# sensor_board_v0_5.net
KiCad netlist of a schematic drawn in EAGLE
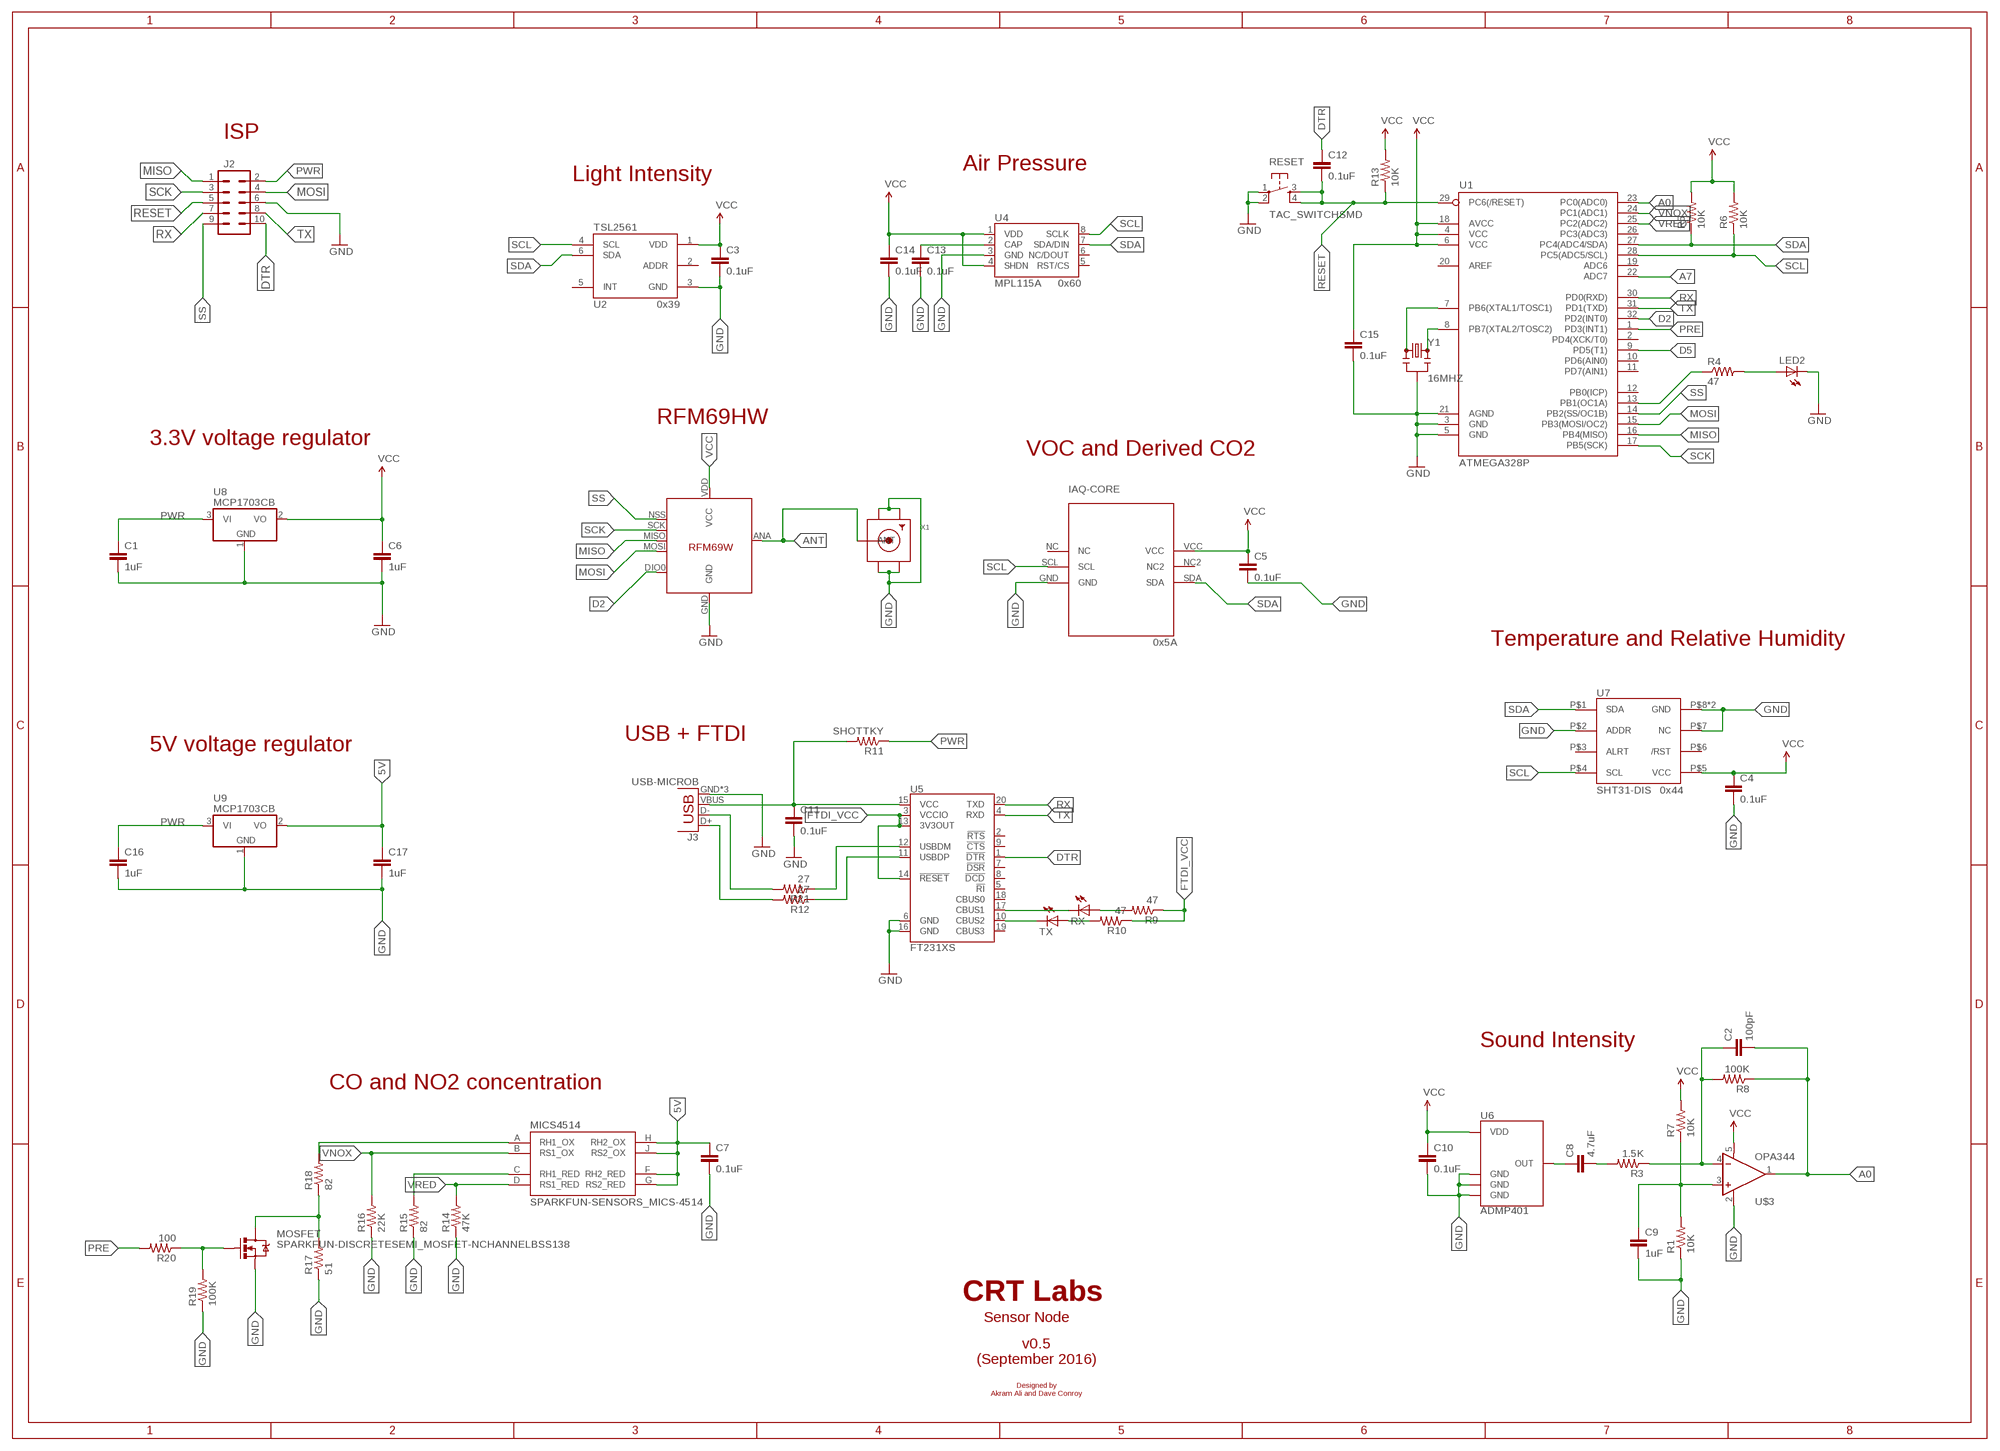
[diagram p0: schematic, sheet 1]

(export (version "E")
  (design (tool "Eeschema 10.0.6"))
  (components
    (comp (ref "C1")
      (value "1uF")
      (footprint "eagle-import:0805")
      (libsource (lib "eagle-import") (part "CAP0805"))
    )
    (comp (ref "C2")
      (value "100pF")
      (footprint "eagle-import:0805")
      (libsource (lib "eagle-import") (part "CAP0805"))
    )
    (comp (ref "C3")
      (value "0.1uF")
      (footprint "eagle-import:0805")
      (libsource (lib "eagle-import") (part "SparkFun-Passives_CAP0805"))
    )
    (comp (ref "C4")
      (value "0.1uF")
      (footprint "eagle-import:0805")
      (libsource (lib "eagle-import") (part "SparkFun-Passives_CAP0805"))
    )
    (comp (ref "C5")
      (value "0.1uF")
      (footprint "eagle-import:0805")
      (libsource (lib "eagle-import") (part "SparkFun-Passives_CAP0805"))
    )
    (comp (ref "C6")
      (value "1uF")
      (footprint "eagle-import:0805")
      (libsource (lib "eagle-import") (part "CAP0805"))
    )
    (comp (ref "C7")
      (value "0.1uF")
      (footprint "eagle-import:0805")
      (libsource (lib "eagle-import") (part "SparkFun-Passives_CAP0805"))
    )
    (comp (ref "C8")
      (value "4.7uF")
      (footprint "eagle-import:0805")
      (libsource (lib "eagle-import") (part "CAP0805"))
    )
    (comp (ref "C9")
      (value "1uF")
      (footprint "eagle-import:0805")
      (libsource (lib "eagle-import") (part "CAP0805"))
    )
    (comp (ref "C10")
      (value "0.1uF")
      (footprint "eagle-import:0805")
      (libsource (lib "eagle-import") (part "CAP0805"))
    )
    (comp (ref "C11")
      (value "0.1uF")
      (footprint "eagle-import:0805")
      (libsource (lib "eagle-import") (part "CAP0805"))
    )
    (comp (ref "C12")
      (value "0.1uF")
      (footprint "eagle-import:0805")
      (libsource (lib "eagle-import") (part "SparkFun-Passives_CAP0805"))
    )
    (comp (ref "C13")
      (value "0.1uF")
      (footprint "eagle-import:0805")
      (libsource (lib "eagle-import") (part "SparkFun-Passives_CAP0805"))
    )
    (comp (ref "C14")
      (value "0.1uF")
      (footprint "eagle-import:0805")
      (libsource (lib "eagle-import") (part "SparkFun-Passives_CAP0805"))
    )
    (comp (ref "C15")
      (value "0.1uF")
      (footprint "eagle-import:0805")
      (libsource (lib "eagle-import") (part "SparkFun-Passives_CAP0805"))
    )
    (comp (ref "C16")
      (value "1uF")
      (footprint "eagle-import:0805")
      (libsource (lib "eagle-import") (part "CAP0805"))
    )
    (comp (ref "C17")
      (value "1uF")
      (footprint "eagle-import:0805")
      (libsource (lib "eagle-import") (part "CAP0805"))
    )
    (comp (ref "IAQ-CORE")
      (value "IAQ-CORE")
      (footprint "eagle-import:IAQ-CORE")
      (fields (field (name "MPN") "IAQ CORE"))
      (libsource (lib "eagle-import") (part "IAQ-CORE"))
    )
    (comp (ref "J2")
      (value "M05X2PTH")
      (footprint "eagle-import:AVR_ICSP")
      (libsource (lib "eagle-import") (part "M05X2PTH"))
    )
    (comp (ref "J3")
      (value "USB-MICROB")
      (footprint "eagle-import:USB-MICROB")
      (libsource (lib "eagle-import") (part "USB-MICROB"))
    )
    (comp (ref "LED2")
      (value "LEDCHIPLED_0805")
      (footprint "eagle-import:CHIPLED_0805")
      (libsource (lib "eagle-import") (part "LEDCHIPLED_0805"))
    )
    (comp (ref "MICS4514")
      (value "SPARKFUN-SENSORS_MICS-4514")
      (footprint "eagle-import:SPARKFUN-SENSORS_MICS_10-SMD")
      (libsource (lib "eagle-import") (part "SPARKFUN-SENSORS_MICS-4514"))
    )
    (comp (ref "MOSFET")
      (value "SPARKFUN-DISCRETESEMI_MOSFET-NCHANNELBSS138")
      (footprint "eagle-import:SPARKFUN-DISCRETESEMI_SOT23-3")
      (libsource (lib "eagle-import") (part "SPARKFUN-DISCRETESEMI_MOSFET-NCHANNELBSS138"))
    )
    (comp (ref "R1")
      (value "10K")
      (footprint "eagle-import:0805")
      (libsource (lib "eagle-import") (part "RESISTOR0805-RES"))
    )
    (comp (ref "R3")
      (value "1.5K")
      (footprint "eagle-import:0805")
      (libsource (lib "eagle-import") (part "RESISTOR0805-RES"))
    )
    (comp (ref "R4")
      (value "47")
      (footprint "eagle-import:0805")
      (libsource (lib "eagle-import") (part "SparkFun-Resistors_RESISTOR0805-RES"))
    )
    (comp (ref "R5")
      (value "10K")
      (footprint "eagle-import:0805")
      (libsource (lib "eagle-import") (part "SparkFun-Resistors_RESISTOR0805-RES"))
    )
    (comp (ref "R6")
      (value "10K")
      (footprint "eagle-import:0805")
      (libsource (lib "eagle-import") (part "SparkFun-Resistors_RESISTOR0805-RES"))
    )
    (comp (ref "R7")
      (value "10K")
      (footprint "eagle-import:0805")
      (libsource (lib "eagle-import") (part "RESISTOR0805-RES"))
    )
    (comp (ref "R8")
      (value "100K")
      (footprint "eagle-import:0805")
      (libsource (lib "eagle-import") (part "RESISTOR0805-RES"))
    )
    (comp (ref "R9")
      (value "47")
      (footprint "eagle-import:0805")
      (libsource (lib "eagle-import") (part "RESISTOR0805-RES"))
    )
    (comp (ref "R10")
      (value "47")
      (footprint "eagle-import:0805")
      (libsource (lib "eagle-import") (part "RESISTOR0805-RES"))
    )
    (comp (ref "R11")
      (value "SHOTTKY")
      (footprint "eagle-import:0805")
      (libsource (lib "eagle-import") (part "RESISTOR0805-RES"))
    )
    (comp (ref "R12")
      (value "27")
      (footprint "eagle-import:0805")
      (libsource (lib "eagle-import") (part "RESISTOR0805-RES"))
    )
    (comp (ref "R13")
      (value "10K")
      (footprint "eagle-import:0805")
      (libsource (lib "eagle-import") (part "RESISTOR0805-RES"))
    )
    (comp (ref "R14")
      (value "47K")
      (footprint "eagle-import:0805")
      (libsource (lib "eagle-import") (part "RESISTOR0805-RES"))
    )
    (comp (ref "R15")
      (value "82")
      (footprint "eagle-import:0805")
      (libsource (lib "eagle-import") (part "RESISTOR0805-RES"))
    )
    (comp (ref "R16")
      (value "22K")
      (footprint "eagle-import:0805")
      (libsource (lib "eagle-import") (part "RESISTOR0805-RES"))
    )
    (comp (ref "R17")
      (value "51")
      (footprint "eagle-import:0805")
      (libsource (lib "eagle-import") (part "RESISTOR0805-RES"))
    )
    (comp (ref "R18")
      (value "82")
      (footprint "eagle-import:0805")
      (libsource (lib "eagle-import") (part "RESISTOR0805-RES"))
    )
    (comp (ref "R19")
      (value "100K")
      (footprint "eagle-import:0805")
      (libsource (lib "eagle-import") (part "RESISTOR0805-RES"))
    )
    (comp (ref "R20")
      (value "100")
      (footprint "eagle-import:0805")
      (libsource (lib "eagle-import") (part "RESISTOR0805-RES"))
    )
    (comp (ref "R21")
      (value "27")
      (footprint "eagle-import:0805")
      (libsource (lib "eagle-import") (part "RESISTOR0805-RES"))
    )
    (comp (ref "RESET")
      (value "TAC_SWITCHSMD")
      (footprint "eagle-import:TACTILE-SWITCH-SMD")
      (libsource (lib "eagle-import") (part "TAC_SWITCHSMD"))
    )
    (comp (ref "RX")
      (value "LEDCHIPLED_0805")
      (footprint "eagle-import:CHIPLED_0805")
      (libsource (lib "eagle-import") (part "LEDCHIPLED_0805"))
    )
    (comp (ref "TX")
      (value "LEDCHIPLED_0805")
      (footprint "eagle-import:CHIPLED_0805")
      (libsource (lib "eagle-import") (part "LEDCHIPLED_0805"))
    )
    (comp (ref "U$3")
      (value "OPA344")
      (footprint "eagle-import:SOT23-5")
      (libsource (lib "eagle-import") (part "OPA344"))
    )
    (comp (ref "U$4")
      (value "RFM69HW")
      (footprint "eagle-import:LOWPOWERLAB_RFM69W-MINPADS")
      (libsource (lib "eagle-import") (part "LOWPOWERLAB_RFM69"))
    )
    (comp (ref "U1")
      (value "ATMEGA328P")
      (footprint "eagle-import:TQFP32-08")
      (fields (field (name "MPN") "ATMEGA328PB-AU"))
      (libsource (lib "eagle-import") (part "ATMEGA328P_TQFP"))
    )
    (comp (ref "U2")
      (value "TSL2561")
      (footprint "eagle-import:FN-6")
      (fields (field (name "MANF") "AMS-TAOS-USA-Inc.") (field (name "MPN") "TSL2561FN"))
      (libsource (lib "eagle-import") (part "TSL2561FN"))
    )
    (comp (ref "U4")
      (value "MPL115A")
      (footprint "eagle-import:LGA8")
      (libsource (lib "eagle-import") (part "MPL115A"))
    )
    (comp (ref "U5")
      (value "FT231XS")
      (footprint "eagle-import:SSOP20_L")
      (libsource (lib "eagle-import") (part "FT231XS"))
    )
    (comp (ref "U6")
      (value "ADMP401")
      (footprint "eagle-import:ADMP401")
      (libsource (lib "eagle-import") (part "ADMP401"))
    )
    (comp (ref "U7")
      (value "SHT31-DIS")
      (footprint "eagle-import:SHT3X")
      (fields (field (name "MPN") "SHT31-DIS-B"))
      (libsource (lib "eagle-import") (part "SHT31-DIS"))
    )
    (comp (ref "U8")
      (value "MCP1703CB")
      (footprint "eagle-import:SOT23")
      (fields (field (name "MPN") "MCP1703T-2502E/CB"))
      (libsource (lib "eagle-import") (part "MCP1703CB"))
    )
    (comp (ref "U9")
      (value "MCP1703CB")
      (footprint "eagle-import:SOT23")
      (fields (field (name "MPN") "MCP1703T-2502E/CB"))
      (libsource (lib "eagle-import") (part "MCP1703CB"))
    )
    (comp (ref "X1")
      (value "SMACONNECTOR_EDGE")
      (footprint "eagle-import:SMA_EDGELAUNCH")
      (libsource (lib "eagle-import") (part "SMACONNECTOR_EDGE"))
    )
    (comp (ref "Y1")
      (value "16MHZ")
      (footprint "eagle-import:RESONATOR-SMD")
      (libsource (lib "eagle-import") (part "RESONATOR16MHZ"))
    )
  )
  (nets
    (net (code "1") (name "5V") (class "Default")
      (node (ref "C17") (pin "1") (pinfunction "1_1") (pintype "passive"))
      (node (ref "C7") (pin "1") (pinfunction "1_1") (pintype "passive"))
      (node (ref "MICS4514") (pin "F") (pinfunction "RH2_RED_F") (pintype "bidirectional"))
      (node (ref "MICS4514") (pin "G") (pinfunction "RS2_RED_G") (pintype "bidirectional"))
      (node (ref "MICS4514") (pin "H") (pinfunction "RH2_OX_H") (pintype "bidirectional"))
      (node (ref "MICS4514") (pin "J") (pinfunction "RS2_OX_J") (pintype "bidirectional"))
      (node (ref "U9") (pin "2") (pinfunction "VO_2") (pintype "passive"))
    )
    (net (code "2") (name "A0") (class "Default")
      (node (ref "C2") (pin "2") (pinfunction "2_2") (pintype "passive"))
      (node (ref "R8") (pin "1") (pinfunction "1_1") (pintype "passive"))
      (node (ref "U$3") (pin "1") (pinfunction "OUT_1") (pintype "output"))
      (node (ref "U1") (pin "23") (pinfunction "PC0(ADC0)_23") (pintype "bidirectional"))
    )
    (net (code "3") (name "A7") (class "Default")
      (node (ref "U1") (pin "22") (pinfunction "ADC7_22") (pintype "bidirectional"))
    )
    (net (code "4") (name "ANT") (class "Default")
      (node (ref "U$4") (pin "ANA") (pinfunction "ANT_ANA") (pintype "passive"))
      (node (ref "X1") (pin "P") (pinfunction "ANT_P") (pintype "bidirectional"))
    )
    (net (code "5") (name "D2") (class "Default")
      (node (ref "U$4") (pin "DIO0") (pinfunction "DIO0_DIO0") (pintype "open_collector"))
      (node (ref "U1") (pin "32") (pinfunction "PD2(INT0)_32") (pintype "bidirectional"))
    )
    (net (code "6") (name "D5") (class "Default")
      (node (ref "U1") (pin "9") (pinfunction "PD5(T1)_9") (pintype "bidirectional"))
    )
    (net (code "7") (name "DTR") (class "Default")
      (node (ref "C12") (pin "1") (pinfunction "1_1") (pintype "passive"))
      (node (ref "J2") (pin "10") (pinfunction "10_10") (pintype "passive"))
      (node (ref "U5") (pin "1") (pinfunction "~{DTR}_1") (pintype "bidirectional"))
    )
    (net (code "8") (name "FTDI_VCC") (class "Default")
      (node (ref "R10") (pin "1") (pinfunction "1_1") (pintype "passive"))
      (node (ref "R9") (pin "1") (pinfunction "1_1") (pintype "passive"))
      (node (ref "U5") (pin "13") (pinfunction "3V3OUT_13") (pintype "bidirectional"))
      (node (ref "U5") (pin "14") (pinfunction "~{RESET}_14") (pintype "bidirectional"))
      (node (ref "U5") (pin "3") (pinfunction "VCCIO_3") (pintype "bidirectional"))
    )
    (net (code "9") (name "GND") (class "Default")
      (node (ref "C1") (pin "2") (pinfunction "2_2") (pintype "passive"))
      (node (ref "C10") (pin "2") (pinfunction "2_2") (pintype "passive"))
      (node (ref "C11") (pin "2") (pinfunction "2_2") (pintype "passive"))
      (node (ref "C13") (pin "2") (pinfunction "2_2") (pintype "passive"))
      (node (ref "C14") (pin "2") (pinfunction "2_2") (pintype "passive"))
      (node (ref "C15") (pin "2") (pinfunction "2_2") (pintype "passive"))
      (node (ref "C16") (pin "2") (pinfunction "2_2") (pintype "passive"))
      (node (ref "C17") (pin "2") (pinfunction "2_2") (pintype "passive"))
      (node (ref "C3") (pin "2") (pinfunction "2_2") (pintype "passive"))
      (node (ref "C4") (pin "2") (pinfunction "2_2") (pintype "passive"))
      (node (ref "C5") (pin "2") (pinfunction "2_2") (pintype "passive"))
      (node (ref "C6") (pin "2") (pinfunction "2_2") (pintype "passive"))
      (node (ref "C7") (pin "2") (pinfunction "2_2") (pintype "passive"))
      (node (ref "C9") (pin "2") (pinfunction "2_2") (pintype "passive"))
      (node (ref "IAQ-CORE") (pin "GND") (pinfunction "GND_GND") (pintype "bidirectional"))
      (node (ref "J2") (pin "6") (pinfunction "6_6") (pintype "passive"))
      (node (ref "J3") (pin "GND") (pinfunction "GND_GND") (pintype "bidirectional"))
      (node (ref "J3") (pin "MT1") (pinfunction "GND_MT1") (pintype "bidirectional"))
      (node (ref "J3") (pin "MT2") (pinfunction "GND_MT2") (pintype "bidirectional"))
      (node (ref "LED2") (pin "C") (pinfunction "C_C") (pintype "passive"))
      (node (ref "MOSFET") (pin "2") (pinfunction "S_2") (pintype "passive"))
      (node (ref "R1") (pin "1") (pinfunction "1_1") (pintype "passive"))
      (node (ref "R14") (pin "1") (pinfunction "1_1") (pintype "passive"))
      (node (ref "R15") (pin "1") (pinfunction "1_1") (pintype "passive"))
      (node (ref "R16") (pin "1") (pinfunction "1_1") (pintype "passive"))
      (node (ref "R17") (pin "1") (pinfunction "1_1") (pintype "passive"))
      (node (ref "R19") (pin "1") (pinfunction "1_1") (pintype "passive"))
      (node (ref "RESET") (pin "1") (pinfunction "1_1") (pintype "passive"))
      (node (ref "RESET") (pin "2") (pinfunction "2_2") (pintype "passive"))
      (node (ref "U$3") (pin "2") (pinfunction "V-_2") (pintype "power_in"))
      (node (ref "U$4") (pin "GND") (pinfunction "GND_GND") (pintype "power_in"))
      (node (ref "U1") (pin "21") (pinfunction "AGND_21") (pintype "bidirectional"))
      (node (ref "U1") (pin "3") (pinfunction "GND_3") (pintype "bidirectional"))
      (node (ref "U1") (pin "5") (pinfunction "GND_5") (pintype "bidirectional"))
      (node (ref "U2") (pin "3") (pinfunction "GND_3") (pintype "power_in"))
      (node (ref "U4") (pin "3") (pinfunction "GND_3") (pintype "bidirectional"))
      (node (ref "U5") (pin "16") (pinfunction "GND_16") (pintype "bidirectional"))
      (node (ref "U5") (pin "6") (pinfunction "GND_6") (pintype "bidirectional"))
      (node (ref "U6") (pin "2") (pinfunction "GND_2") (pintype "bidirectional"))
      (node (ref "U6") (pin "4") (pinfunction "GND_4") (pintype "bidirectional"))
      (node (ref "U6") (pin "6") (pinfunction "GND_6") (pintype "bidirectional"))
      (node (ref "U7") (pin "P$2") (pinfunction "ADDR_P$2") (pintype "bidirectional"))
      (node (ref "U7") (pin "P$7") (pinfunction "NC_P$7") (pintype "bidirectional"))
      (node (ref "U7") (pin "P$8") (pinfunction "GND_P$8") (pintype "bidirectional"))
      (node (ref "U7") (pin "PAD") (pinfunction "GND_PAD") (pintype "bidirectional"))
      (node (ref "U8") (pin "1") (pinfunction "GND_1") (pintype "passive"))
      (node (ref "U9") (pin "1") (pinfunction "GND_1") (pintype "passive"))
      (node (ref "X1") (pin "GND@1") (pinfunction "GND4_GND@1") (pintype "power_in"))
      (node (ref "X1") (pin "GND@2") (pinfunction "GND3_GND@2") (pintype "power_in"))
      (node (ref "X1") (pin "GND@3") (pinfunction "GND2_GND@3") (pintype "power_in"))
      (node (ref "X1") (pin "GND@4") (pinfunction "GND1_GND@4") (pintype "power_in"))
      (node (ref "Y1") (pin "2") (pinfunction "2_2") (pintype "passive"))
    )
    (net (code "10") (name "MISO") (class "Default")
      (node (ref "J2") (pin "1") (pinfunction "1_1") (pintype "passive"))
      (node (ref "U$4") (pin "MISO") (pinfunction "MISO_MISO") (pintype "input"))
      (node (ref "U1") (pin "16") (pinfunction "PB4(MISO)_16") (pintype "bidirectional"))
    )
    (net (code "11") (name "MOSI") (class "Default")
      (node (ref "J2") (pin "4") (pinfunction "4_4") (pintype "passive"))
      (node (ref "U$4") (pin "MOSI") (pinfunction "MOSI_MOSI") (pintype "output"))
      (node (ref "U1") (pin "15") (pinfunction "PB3(MOSI/OC2)_15") (pintype "bidirectional"))
    )
    (net (code "12") (name "Net-(C8-Pad2)") (class "Default")
      (node (ref "C8") (pin "2") (pinfunction "2_2") (pintype "passive"))
      (node (ref "R3") (pin "2") (pinfunction "2_2") (pintype "passive"))
    )
    (net (code "13") (name "Net-(J3-PadD+)") (class "Default")
      (node (ref "J3") (pin "D+") (pinfunction "D+_D+") (pintype "bidirectional"))
      (node (ref "R12") (pin "2") (pinfunction "2_2") (pintype "passive"))
    )
    (net (code "14") (name "Net-(J3-PadD-)") (class "Default")
      (node (ref "J3") (pin "D-") (pinfunction "D-_D-") (pintype "bidirectional"))
      (node (ref "R21") (pin "2") (pinfunction "2_2") (pintype "passive"))
    )
    (net (code "15") (name "Net-(LED2-PadA)") (class "Default")
      (node (ref "LED2") (pin "A") (pinfunction "A_A") (pintype "passive"))
      (node (ref "R4") (pin "2") (pinfunction "2_2") (pintype "passive"))
    )
    (net (code "16") (name "Net-(MICS4514-RH1_OX)") (class "Default")
      (node (ref "MICS4514") (pin "A") (pinfunction "RH1_OX_A") (pintype "bidirectional"))
      (node (ref "R18") (pin "2") (pinfunction "2_2") (pintype "passive"))
    )
    (net (code "17") (name "Net-(MICS4514-RH1_RED)") (class "Default")
      (node (ref "MICS4514") (pin "C") (pinfunction "RH1_RED_C") (pintype "bidirectional"))
      (node (ref "R15") (pin "2") (pinfunction "2_2") (pintype "passive"))
    )
    (net (code "18") (name "Net-(MOSFET-D)") (class "Default")
      (node (ref "MOSFET") (pin "3") (pinfunction "D_3") (pintype "passive"))
      (node (ref "R17") (pin "2") (pinfunction "2_2") (pintype "passive"))
      (node (ref "R18") (pin "1") (pinfunction "1_1") (pintype "passive"))
    )
    (net (code "19") (name "Net-(MOSFET-G)") (class "Default")
      (node (ref "MOSFET") (pin "1") (pinfunction "G_1") (pintype "passive"))
      (node (ref "R19") (pin "2") (pinfunction "2_2") (pintype "passive"))
      (node (ref "R20") (pin "1") (pinfunction "1_1") (pintype "passive"))
    )
    (net (code "20") (name "Net-(R9-Pad2)") (class "Default")
      (node (ref "R9") (pin "2") (pinfunction "2_2") (pintype "passive"))
      (node (ref "RX") (pin "A") (pinfunction "A_A") (pintype "passive"))
    )
    (net (code "21") (name "Net-(R10-Pad2)") (class "Default")
      (node (ref "R10") (pin "2") (pinfunction "2_2") (pintype "passive"))
      (node (ref "TX") (pin "A") (pinfunction "A_A") (pintype "passive"))
    )
    (net (code "22") (name "Net-(U$3-+IN)") (class "Default")
      (node (ref "C9") (pin "1") (pinfunction "1_1") (pintype "passive"))
      (node (ref "R1") (pin "2") (pinfunction "2_2") (pintype "passive"))
      (node (ref "R7") (pin "1") (pinfunction "1_1") (pintype "passive"))
      (node (ref "U$3") (pin "3") (pinfunction "+IN_3") (pintype "input"))
    )
    (net (code "23") (name "Net-(U$3--IN)") (class "Default")
      (node (ref "C2") (pin "1") (pinfunction "1_1") (pintype "passive"))
      (node (ref "R3") (pin "1") (pinfunction "1_1") (pintype "passive"))
      (node (ref "R8") (pin "2") (pinfunction "2_2") (pintype "passive"))
      (node (ref "U$3") (pin "4") (pinfunction "-IN_4") (pintype "input"))
    )
    (net (code "24") (name "Net-(U1-PB1(OC1A))") (class "Default")
      (node (ref "R4") (pin "1") (pinfunction "1_1") (pintype "passive"))
      (node (ref "U1") (pin "13") (pinfunction "PB1(OC1A)_13") (pintype "bidirectional"))
    )
    (net (code "25") (name "Net-(U1-PB6(XTAL1{slash}TOSC1))") (class "Default")
      (node (ref "U1") (pin "7") (pinfunction "PB6(XTAL1/TOSC1)_7") (pintype "bidirectional"))
      (node (ref "Y1") (pin "1") (pinfunction "1_1") (pintype "passive"))
    )
    (net (code "26") (name "Net-(U1-PB7(XTAL2{slash}TOSC2))") (class "Default")
      (node (ref "U1") (pin "8") (pinfunction "PB7(XTAL2/TOSC2)_8") (pintype "bidirectional"))
      (node (ref "Y1") (pin "3") (pinfunction "3_3") (pintype "passive"))
    )
    (net (code "27") (name "Net-(U4-CAP)") (class "Default")
      (node (ref "C13") (pin "1") (pinfunction "1_1") (pintype "passive"))
      (node (ref "U4") (pin "2") (pinfunction "CAP_2") (pintype "bidirectional"))
    )
    (net (code "28") (name "Net-(U5-CBUS1)") (class "Default")
      (node (ref "RX") (pin "C") (pinfunction "C_C") (pintype "passive"))
      (node (ref "U5") (pin "17") (pinfunction "CBUS1_17") (pintype "bidirectional"))
    )
    (net (code "29") (name "Net-(U5-CBUS2)") (class "Default")
      (node (ref "TX") (pin "C") (pinfunction "C_C") (pintype "passive"))
      (node (ref "U5") (pin "10") (pinfunction "CBUS2_10") (pintype "bidirectional"))
    )
    (net (code "30") (name "Net-(U5-USBDM)") (class "Default")
      (node (ref "R21") (pin "1") (pinfunction "1_1") (pintype "passive"))
      (node (ref "U5") (pin "12") (pinfunction "USBDM_12") (pintype "bidirectional"))
    )
    (net (code "31") (name "Net-(U5-USBDP)") (class "Default")
      (node (ref "R12") (pin "1") (pinfunction "1_1") (pintype "passive"))
      (node (ref "U5") (pin "11") (pinfunction "USBDP_11") (pintype "bidirectional"))
    )
    (net (code "32") (name "Net-(U5-VCC)") (class "Default")
      (node (ref "C11") (pin "1") (pinfunction "1_1") (pintype "passive"))
      (node (ref "J3") (pin "VBUS") (pinfunction "VBUS_VBUS") (pintype "bidirectional"))
      (node (ref "R11") (pin "2") (pinfunction "2_2") (pintype "passive"))
      (node (ref "U5") (pin "15") (pinfunction "VCC_15") (pintype "bidirectional"))
    )
    (net (code "33") (name "Net-(U6-OUT)") (class "Default")
      (node (ref "C8") (pin "1") (pinfunction "1_1") (pintype "passive"))
      (node (ref "U6") (pin "1") (pinfunction "OUT_1") (pintype "bidirectional"))
    )
    (net (code "34") (name "PRE") (class "Default")
      (node (ref "R20") (pin "2") (pinfunction "2_2") (pintype "passive"))
      (node (ref "U1") (pin "1") (pinfunction "PD3(INT1)_1") (pintype "bidirectional"))
    )
    (net (code "35") (name "PWR") (class "Default")
      (node (ref "C1") (pin "1") (pinfunction "1_1") (pintype "passive"))
      (node (ref "C16") (pin "1") (pinfunction "1_1") (pintype "passive"))
      (node (ref "J2") (pin "2") (pinfunction "2_2") (pintype "passive"))
      (node (ref "R11") (pin "1") (pinfunction "1_1") (pintype "passive"))
      (node (ref "U8") (pin "3") (pinfunction "VI_3") (pintype "input"))
      (node (ref "U9") (pin "3") (pinfunction "VI_3") (pintype "input"))
    )
    (net (code "36") (name "RESET") (class "Default")
      (node (ref "C12") (pin "2") (pinfunction "2_2") (pintype "passive"))
      (node (ref "J2") (pin "5") (pinfunction "5_5") (pintype "passive"))
      (node (ref "R13") (pin "1") (pinfunction "1_1") (pintype "passive"))
      (node (ref "RESET") (pin "3") (pinfunction "3_3") (pintype "passive"))
      (node (ref "RESET") (pin "4") (pinfunction "4_4") (pintype "passive"))
      (node (ref "U1") (pin "29") (pinfunction "PC6(/RESET)_29") (pintype "bidirectional"))
    )
    (net (code "37") (name "RX") (class "Default")
      (node (ref "J2") (pin "7") (pinfunction "7_7") (pintype "passive"))
      (node (ref "U1") (pin "30") (pinfunction "PD0(RXD)_30") (pintype "bidirectional"))
      (node (ref "U5") (pin "20") (pinfunction "TXD_20") (pintype "bidirectional"))
    )
    (net (code "38") (name "SCK") (class "Default")
      (node (ref "J2") (pin "3") (pinfunction "3_3") (pintype "passive"))
      (node (ref "U$4") (pin "SCK") (pinfunction "SCK_SCK") (pintype "input"))
      (node (ref "U1") (pin "17") (pinfunction "PB5(SCK)_17") (pintype "bidirectional"))
    )
    (net (code "39") (name "SCL") (class "Default")
      (node (ref "IAQ-CORE") (pin "SCL") (pinfunction "SCL_SCL") (pintype "bidirectional"))
      (node (ref "R6") (pin "1") (pinfunction "1_1") (pintype "passive"))
      (node (ref "U1") (pin "28") (pinfunction "PC5(ADC5/SCL)_28") (pintype "bidirectional"))
      (node (ref "U2") (pin "4") (pinfunction "SCL_4") (pintype "input"))
      (node (ref "U4") (pin "8") (pinfunction "SCLK_8") (pintype "bidirectional"))
      (node (ref "U7") (pin "P$4") (pinfunction "SCL_P$4") (pintype "bidirectional"))
    )
    (net (code "40") (name "SDA") (class "Default")
      (node (ref "IAQ-CORE") (pin "SDA") (pinfunction "SDA_SDA") (pintype "bidirectional"))
      (node (ref "R5") (pin "1") (pinfunction "1_1") (pintype "passive"))
      (node (ref "U1") (pin "27") (pinfunction "PC4(ADC4/SDA)_27") (pintype "bidirectional"))
      (node (ref "U2") (pin "6") (pinfunction "SDA_6") (pintype "bidirectional"))
      (node (ref "U4") (pin "7") (pinfunction "SDA/DIN_7") (pintype "bidirectional"))
      (node (ref "U7") (pin "P$1") (pinfunction "SDA_P$1") (pintype "bidirectional"))
    )
    (net (code "41") (name "SS") (class "Default")
      (node (ref "J2") (pin "9") (pinfunction "9_9") (pintype "passive"))
      (node (ref "U$4") (pin "NSS") (pinfunction "SEL_NSS") (pintype "input"))
      (node (ref "U1") (pin "14") (pinfunction "PB2(SS/OC1B)_14") (pintype "bidirectional"))
    )
    (net (code "42") (name "TX") (class "Default")
      (node (ref "J2") (pin "8") (pinfunction "8_8") (pintype "passive"))
      (node (ref "U1") (pin "31") (pinfunction "PD1(TXD)_31") (pintype "bidirectional"))
      (node (ref "U5") (pin "4") (pinfunction "RXD_4") (pintype "bidirectional"))
    )
    (net (code "43") (name "VCC") (class "Default")
      (node (ref "C10") (pin "1") (pinfunction "1_1") (pintype "passive"))
      (node (ref "C14") (pin "1") (pinfunction "1_1") (pintype "passive"))
      (node (ref "C15") (pin "1") (pinfunction "1_1") (pintype "passive"))
      (node (ref "C3") (pin "1") (pinfunction "1_1") (pintype "passive"))
      (node (ref "C4") (pin "1") (pinfunction "1_1") (pintype "passive"))
      (node (ref "C5") (pin "1") (pinfunction "1_1") (pintype "passive"))
      (node (ref "C6") (pin "1") (pinfunction "1_1") (pintype "passive"))
      (node (ref "IAQ-CORE") (pin "VCC") (pinfunction "VCC_VCC") (pintype "bidirectional"))
      (node (ref "R13") (pin "2") (pinfunction "2_2") (pintype "passive"))
      (node (ref "R5") (pin "2") (pinfunction "2_2") (pintype "passive"))
      (node (ref "R6") (pin "2") (pinfunction "2_2") (pintype "passive"))
      (node (ref "R7") (pin "2") (pinfunction "2_2") (pintype "passive"))
      (node (ref "U$3") (pin "5") (pinfunction "V+_5") (pintype "power_in"))
      (node (ref "U$4") (pin "VDD") (pinfunction "VCC_VDD") (pintype "power_in"))
      (node (ref "U1") (pin "18") (pinfunction "AVCC_18") (pintype "bidirectional"))
      (node (ref "U1") (pin "4") (pinfunction "VCC_4") (pintype "bidirectional"))
      (node (ref "U1") (pin "6") (pinfunction "VCC_6") (pintype "bidirectional"))
      (node (ref "U2") (pin "1") (pinfunction "VDD_1") (pintype "power_in"))
      (node (ref "U4") (pin "1") (pinfunction "VDD_1") (pintype "bidirectional"))
      (node (ref "U4") (pin "4") (pinfunction "SHDN_4") (pintype "bidirectional"))
      (node (ref "U6") (pin "5") (pinfunction "VDD_5") (pintype "bidirectional"))
      (node (ref "U7") (pin "P$5") (pinfunction "VCC_P$5") (pintype "bidirectional"))
      (node (ref "U8") (pin "2") (pinfunction "VO_2") (pintype "passive"))
    )
    (net (code "44") (name "VNOX") (class "Default")
      (node (ref "MICS4514") (pin "B") (pinfunction "RS1_OX_B") (pintype "bidirectional"))
      (node (ref "R16") (pin "2") (pinfunction "2_2") (pintype "passive"))
      (node (ref "U1") (pin "24") (pinfunction "PC1(ADC1)_24") (pintype "bidirectional"))
    )
    (net (code "45") (name "VRED") (class "Default")
      (node (ref "MICS4514") (pin "D") (pinfunction "RS1_RED_D") (pintype "bidirectional"))
      (node (ref "R14") (pin "2") (pinfunction "2_2") (pintype "passive"))
      (node (ref "U1") (pin "25") (pinfunction "PC2(ADC2)_25") (pintype "bidirectional"))
    )
    (net (code "46") (name "unconnected-(IAQ-CORE-PadNC)") (class "Default")
      (node (ref "IAQ-CORE") (pin "NC") (pinfunction "NC_NC") (pintype "bidirectional"))
    )
    (net (code "47") (name "unconnected-(IAQ-CORE-PadNC2)") (class "Default")
      (node (ref "IAQ-CORE") (pin "NC2") (pinfunction "NC2_NC2") (pintype "bidirectional"))
    )
    (net (code "48") (name "unconnected-(U1-ADC6-Pad19)") (class "Default")
      (node (ref "U1") (pin "19") (pinfunction "ADC6_19") (pintype "bidirectional"))
    )
    (net (code "49") (name "unconnected-(U1-AREF-Pad20)") (class "Default")
      (node (ref "U1") (pin "20") (pinfunction "AREF_20") (pintype "bidirectional"))
    )
    (net (code "50") (name "unconnected-(U1-PB0(ICP)-Pad12)") (class "Default")
      (node (ref "U1") (pin "12") (pinfunction "PB0(ICP)_12") (pintype "bidirectional"))
    )
    (net (code "51") (name "unconnected-(U1-PC3(ADC3)-Pad26)") (class "Default")
      (node (ref "U1") (pin "26") (pinfunction "PC3(ADC3)_26") (pintype "bidirectional"))
    )
    (net (code "52") (name "unconnected-(U1-PD4(XCK{slash}T0)-Pad2)") (class "Default")
      (node (ref "U1") (pin "2") (pinfunction "PD4(XCK/T0)_2") (pintype "bidirectional"))
    )
    (net (code "53") (name "unconnected-(U1-PD6(AIN0)-Pad10)") (class "Default")
      (node (ref "U1") (pin "10") (pinfunction "PD6(AIN0)_10") (pintype "bidirectional"))
    )
    (net (code "54") (name "unconnected-(U1-PD7(AIN1)-Pad11)") (class "Default")
      (node (ref "U1") (pin "11") (pinfunction "PD7(AIN1)_11") (pintype "bidirectional"))
    )
    (net (code "55") (name "unconnected-(U2-ADDR-Pad2)") (class "Default")
      (node (ref "U2") (pin "2") (pinfunction "ADDR_2") (pintype "input"))
    )
    (net (code "56") (name "unconnected-(U2-INT-Pad5)") (class "Default")
      (node (ref "U2") (pin "5") (pinfunction "INT_5") (pintype "output"))
    )
    (net (code "57") (name "unconnected-(U4-NC{slash}DOUT-Pad6)") (class "Default")
      (node (ref "U4") (pin "6") (pinfunction "NC/DOUT_6") (pintype "bidirectional"))
    )
    (net (code "58") (name "unconnected-(U4-RST{slash}CS-Pad5)") (class "Default")
      (node (ref "U4") (pin "5") (pinfunction "RST/CS_5") (pintype "bidirectional"))
    )
    (net (code "59") (name "unconnected-(U5-CBUS0-Pad18)") (class "Default")
      (node (ref "U5") (pin "18") (pinfunction "CBUS0_18") (pintype "bidirectional"))
    )
    (net (code "60") (name "unconnected-(U5-CBUS3-Pad19)") (class "Default")
      (node (ref "U5") (pin "19") (pinfunction "CBUS3_19") (pintype "bidirectional"))
    )
    (net (code "61") (name "unconnected-(U5-~{CTS}-Pad9)") (class "Default")
      (node (ref "U5") (pin "9") (pinfunction "~{CTS}_9") (pintype "bidirectional"))
    )
    (net (code "62") (name "unconnected-(U5-~{DCD}-Pad8)") (class "Default")
      (node (ref "U5") (pin "8") (pinfunction "~{DCD}_8") (pintype "bidirectional"))
    )
    (net (code "63") (name "unconnected-(U5-~{DSR}-Pad7)") (class "Default")
      (node (ref "U5") (pin "7") (pinfunction "~{DSR}_7") (pintype "bidirectional"))
    )
    (net (code "64") (name "unconnected-(U5-~{RI}-Pad5)") (class "Default")
      (node (ref "U5") (pin "5") (pinfunction "~{RI}_5") (pintype "bidirectional"))
    )
    (net (code "65") (name "unconnected-(U5-~{RTS}-Pad2)") (class "Default")
      (node (ref "U5") (pin "2") (pinfunction "~{RTS}_2") (pintype "bidirectional"))
    )
    (net (code "66") (name "unconnected-(U7-ALRT-PadP$3)") (class "Default")
      (node (ref "U7") (pin "P$3") (pinfunction "ALRT_P$3") (pintype "bidirectional"))
    )
    (net (code "67") (name "unconnected-(U7-{slash}RST-PadP$6)") (class "Default")
      (node (ref "U7") (pin "P$6") (pinfunction "/RST_P$6") (pintype "bidirectional"))
    )
  )
)
